# Sheet1.net
KiCad netlist of a schematic drawn in Altium Designer
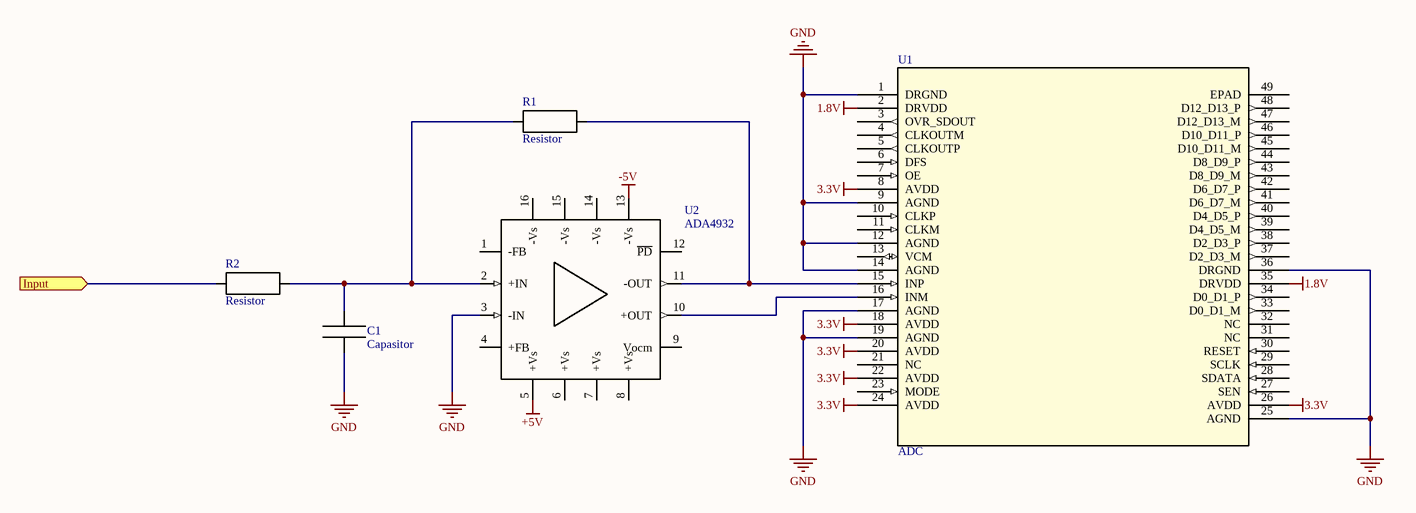
[diagram p0: Sheet1.SchDoc]

(export (version "E")
  (design (tool "Eeschema 10.0.6"))
  (components
    (comp (ref "C1") (value "Capasitor") (libsource (lib "Resistor") (part "Capasitor")))
    (comp (ref "R1")
      (value "Resistor")
      (footprint "Zadanie:Resistor")
      (libsource (lib "Resistor") (part "Resistor"))
    )
    (comp (ref "R2")
      (value "Resistor")
      (footprint "Zadanie:Resistor")
      (libsource (lib "Resistor") (part "Resistor"))
    )
    (comp (ref "U1") (value "ADC") (footprint "Zadanie:ADC") (libsource (lib "Resistor") (part "ADC")))
    (comp (ref "U2") (value "ADA4932") (footprint "Zadanie:AD") (libsource (lib "Resistor") (part "ADA4932")))
  )
  (nets
    (net (code "1") (name "+5V") (class "Default")
      (node (ref "U2") (pin "5") (pinfunction "+Vs_5") (pintype "power_in"))
    )
    (net (code "2") (name "-5V") (class "Default")
      (node (ref "U2") (pin "13") (pinfunction "-Vs_13") (pintype "power_in"))
    )
    (net (code "3") (name "/Input") (class "Default")
      (node (ref "R2") (pin "1") (pinfunction "1_1") (pintype "passive"))
    )
    (net (code "4") (name "1.8V") (class "Default")
      (node (ref "U1") (pin "2") (pinfunction "DRVDD_2") (pintype "power_in"))
      (node (ref "U1") (pin "35") (pinfunction "DRVDD_35") (pintype "power_in"))
    )
    (net (code "5") (name "3.3V") (class "Default")
      (node (ref "U1") (pin "18") (pinfunction "AVDD_18") (pintype "power_in"))
      (node (ref "U1") (pin "20") (pinfunction "AVDD_20") (pintype "power_in"))
      (node (ref "U1") (pin "22") (pinfunction "AVDD_22") (pintype "power_in"))
      (node (ref "U1") (pin "24") (pinfunction "AVDD_24") (pintype "power_in"))
      (node (ref "U1") (pin "26") (pinfunction "AVDD_26") (pintype "power_in"))
      (node (ref "U1") (pin "8") (pinfunction "AVDD_8") (pintype "power_in"))
    )
    (net (code "6") (name "GND") (class "Default")
      (node (ref "C1") (pin "0") (pinfunction "0_0") (pintype "passive"))
      (node (ref "U1") (pin "1") (pinfunction "DRGND_1") (pintype "power_in"))
      (node (ref "U1") (pin "12") (pinfunction "AGND_12") (pintype "power_in"))
      (node (ref "U1") (pin "14") (pinfunction "AGND_14") (pintype "power_in"))
      (node (ref "U1") (pin "17") (pinfunction "AGND_17") (pintype "power_in"))
      (node (ref "U1") (pin "19") (pinfunction "AGND_19") (pintype "power_in"))
      (node (ref "U1") (pin "25") (pinfunction "AGND_25") (pintype "power_in"))
      (node (ref "U1") (pin "36") (pinfunction "DRGND_36") (pintype "power_in"))
      (node (ref "U1") (pin "9") (pinfunction "AGND_9") (pintype "power_in"))
      (node (ref "U2") (pin "3") (pinfunction "-IN_3") (pintype "input"))
    )
    (net (code "7") (name "Net-(U1-INM)") (class "Default")
      (node (ref "U1") (pin "16") (pinfunction "INM_16") (pintype "input"))
      (node (ref "U2") (pin "10") (pinfunction "+OUT_10") (pintype "output"))
    )
    (net (code "8") (name "Net-(U1-INP)") (class "Default")
      (node (ref "R1") (pin "2") (pinfunction "2_2") (pintype "passive"))
      (node (ref "U1") (pin "15") (pinfunction "INP_15") (pintype "input"))
      (node (ref "U2") (pin "11") (pinfunction "-OUT_11") (pintype "output"))
    )
    (net (code "9") (name "Net-(U2-+IN)") (class "Default")
      (node (ref "C1") (pin "1") (pinfunction "1_1") (pintype "passive"))
      (node (ref "R1") (pin "1") (pinfunction "1_1") (pintype "passive"))
      (node (ref "R2") (pin "2") (pinfunction "2_2") (pintype "passive"))
      (node (ref "U2") (pin "2") (pinfunction "+IN_2") (pintype "input"))
    )
    (net (code "10") (name "unconnected-(U1-CLKM-Pad11)") (class "Default")
      (node (ref "U1") (pin "11") (pinfunction "CLKM_11") (pintype "input"))
    )
    (net (code "11") (name "unconnected-(U1-CLKOUTM-Pad4)") (class "Default")
      (node (ref "U1") (pin "4") (pinfunction "CLKOUTM_4") (pintype "output"))
    )
    (net (code "12") (name "unconnected-(U1-CLKOUTP-Pad5)") (class "Default")
      (node (ref "U1") (pin "5") (pinfunction "CLKOUTP_5") (pintype "output"))
    )
    (net (code "13") (name "unconnected-(U1-CLKP-Pad10)") (class "Default")
      (node (ref "U1") (pin "10") (pinfunction "CLKP_10") (pintype "input"))
    )
    (net (code "14") (name "unconnected-(U1-D0_D1_M-Pad33)") (class "Default")
      (node (ref "U1") (pin "33") (pinfunction "D0_D1_M_33") (pintype "output"))
    )
    (net (code "15") (name "unconnected-(U1-D0_D1_P-Pad34)") (class "Default")
      (node (ref "U1") (pin "34") (pinfunction "D0_D1_P_34") (pintype "output"))
    )
    (net (code "16") (name "unconnected-(U1-D2_D3_M-Pad37)") (class "Default")
      (node (ref "U1") (pin "37") (pinfunction "D2_D3_M_37") (pintype "output"))
    )
    (net (code "17") (name "unconnected-(U1-D2_D3_P-Pad38)") (class "Default")
      (node (ref "U1") (pin "38") (pinfunction "D2_D3_P_38") (pintype "output"))
    )
    (net (code "18") (name "unconnected-(U1-D4_D5_M-Pad39)") (class "Default")
      (node (ref "U1") (pin "39") (pinfunction "D4_D5_M_39") (pintype "output"))
    )
    (net (code "19") (name "unconnected-(U1-D4_D5_P-Pad40)") (class "Default")
      (node (ref "U1") (pin "40") (pinfunction "D4_D5_P_40") (pintype "output"))
    )
    (net (code "20") (name "unconnected-(U1-D6_D7_M-Pad41)") (class "Default")
      (node (ref "U1") (pin "41") (pinfunction "D6_D7_M_41") (pintype "output"))
    )
    (net (code "21") (name "unconnected-(U1-D6_D7_P-Pad42)") (class "Default")
      (node (ref "U1") (pin "42") (pinfunction "D6_D7_P_42") (pintype "output"))
    )
    (net (code "22") (name "unconnected-(U1-D8_D9_M-Pad43)") (class "Default")
      (node (ref "U1") (pin "43") (pinfunction "D8_D9_M_43") (pintype "output"))
    )
    (net (code "23") (name "unconnected-(U1-D8_D9_P-Pad44)") (class "Default")
      (node (ref "U1") (pin "44") (pinfunction "D8_D9_P_44") (pintype "output"))
    )
    (net (code "24") (name "unconnected-(U1-D10_D11_M-Pad45)") (class "Default")
      (node (ref "U1") (pin "45") (pinfunction "D10_D11_M_45") (pintype "output"))
    )
    (net (code "25") (name "unconnected-(U1-D10_D11_P-Pad46)") (class "Default")
      (node (ref "U1") (pin "46") (pinfunction "D10_D11_P_46") (pintype "output"))
    )
    (net (code "26") (name "unconnected-(U1-D12_D13_M-Pad47)") (class "Default")
      (node (ref "U1") (pin "47") (pinfunction "D12_D13_M_47") (pintype "output"))
    )
    (net (code "27") (name "unconnected-(U1-D12_D13_P-Pad48)") (class "Default")
      (node (ref "U1") (pin "48") (pinfunction "D12_D13_P_48") (pintype "output"))
    )
    (net (code "28") (name "unconnected-(U1-DFS-Pad6)") (class "Default")
      (node (ref "U1") (pin "6") (pinfunction "DFS_6") (pintype "input"))
    )
    (net (code "29") (name "unconnected-(U1-EPAD-Pad49)") (class "Default")
      (node (ref "U1") (pin "49") (pinfunction "EPAD_49") (pintype "power_in"))
    )
    (net (code "30") (name "unconnected-(U1-MODE-Pad23)") (class "Default")
      (node (ref "U1") (pin "23") (pinfunction "MODE_23") (pintype "input"))
    )
    (net (code "31") (name "unconnected-(U1-NC-Pad21)") (class "Default")
      (node (ref "U1") (pin "21") (pinfunction "NC_21") (pintype "passive"))
    )
    (net (code "32") (name "unconnected-(U1-NC-Pad31)") (class "Default")
      (node (ref "U1") (pin "31") (pinfunction "NC_31") (pintype "passive"))
    )
    (net (code "33") (name "unconnected-(U1-NC-Pad32)") (class "Default")
      (node (ref "U1") (pin "32") (pinfunction "NC_32") (pintype "passive"))
    )
    (net (code "34") (name "unconnected-(U1-OE-Pad7)") (class "Default")
      (node (ref "U1") (pin "7") (pinfunction "OE_7") (pintype "input"))
    )
    (net (code "35") (name "unconnected-(U1-OVR_SDOUT-Pad3)") (class "Default")
      (node (ref "U1") (pin "3") (pinfunction "OVR_SDOUT_3") (pintype "output"))
    )
    (net (code "36") (name "unconnected-(U1-RESET-Pad30)") (class "Default")
      (node (ref "U1") (pin "30") (pinfunction "RESET_30") (pintype "input"))
    )
    (net (code "37") (name "unconnected-(U1-SCLK-Pad29)") (class "Default")
      (node (ref "U1") (pin "29") (pinfunction "SCLK_29") (pintype "input"))
    )
    (net (code "38") (name "unconnected-(U1-SDATA-Pad28)") (class "Default")
      (node (ref "U1") (pin "28") (pinfunction "SDATA_28") (pintype "input"))
    )
    (net (code "39") (name "unconnected-(U1-SEN-Pad27)") (class "Default")
      (node (ref "U1") (pin "27") (pinfunction "SEN_27") (pintype "input"))
    )
    (net (code "40") (name "unconnected-(U1-VCM-Pad13)") (class "Default")
      (node (ref "U1") (pin "13") (pinfunction "VCM_13") (pintype "bidirectional"))
    )
    (net (code "41") (name "unconnected-(U2-+FB-Pad4)") (class "Default")
      (node (ref "U2") (pin "4") (pinfunction "+FB_4") (pintype "passive"))
    )
    (net (code "42") (name "unconnected-(U2-+Vs-Pad6)") (class "Default")
      (node (ref "U2") (pin "6") (pinfunction "+Vs_6") (pintype "power_in"))
    )
    (net (code "43") (name "unconnected-(U2-+Vs-Pad7)") (class "Default")
      (node (ref "U2") (pin "7") (pinfunction "+Vs_7") (pintype "power_in"))
    )
    (net (code "44") (name "unconnected-(U2-+Vs-Pad8)") (class "Default")
      (node (ref "U2") (pin "8") (pinfunction "+Vs_8") (pintype "power_in"))
    )
    (net (code "45") (name "unconnected-(U2--FB-Pad1)") (class "Default")
      (node (ref "U2") (pin "1") (pinfunction "-FB_1") (pintype "passive"))
    )
    (net (code "46") (name "unconnected-(U2--Vs-Pad14)") (class "Default")
      (node (ref "U2") (pin "14") (pinfunction "-Vs_14") (pintype "power_in"))
    )
    (net (code "47") (name "unconnected-(U2--Vs-Pad15)") (class "Default")
      (node (ref "U2") (pin "15") (pinfunction "-Vs_15") (pintype "power_in"))
    )
    (net (code "48") (name "unconnected-(U2--Vs-Pad16)") (class "Default")
      (node (ref "U2") (pin "16") (pinfunction "-Vs_16") (pintype "power_in"))
    )
    (net (code "49") (name "unconnected-(U2-Vocm-Pad9)") (class "Default")
      (node (ref "U2") (pin "9") (pinfunction "Vocm_9") (pintype "passive"))
    )
    (net (code "50") (name "unconnected-(U2-~{PD}-Pad12)") (class "Default")
      (node (ref "U2") (pin "12") (pinfunction "~{PD}_12") (pintype "passive"))
    )
  )
)
